# Micro_Controller.net
KiCad netlist of a schematic drawn in Altium Designer
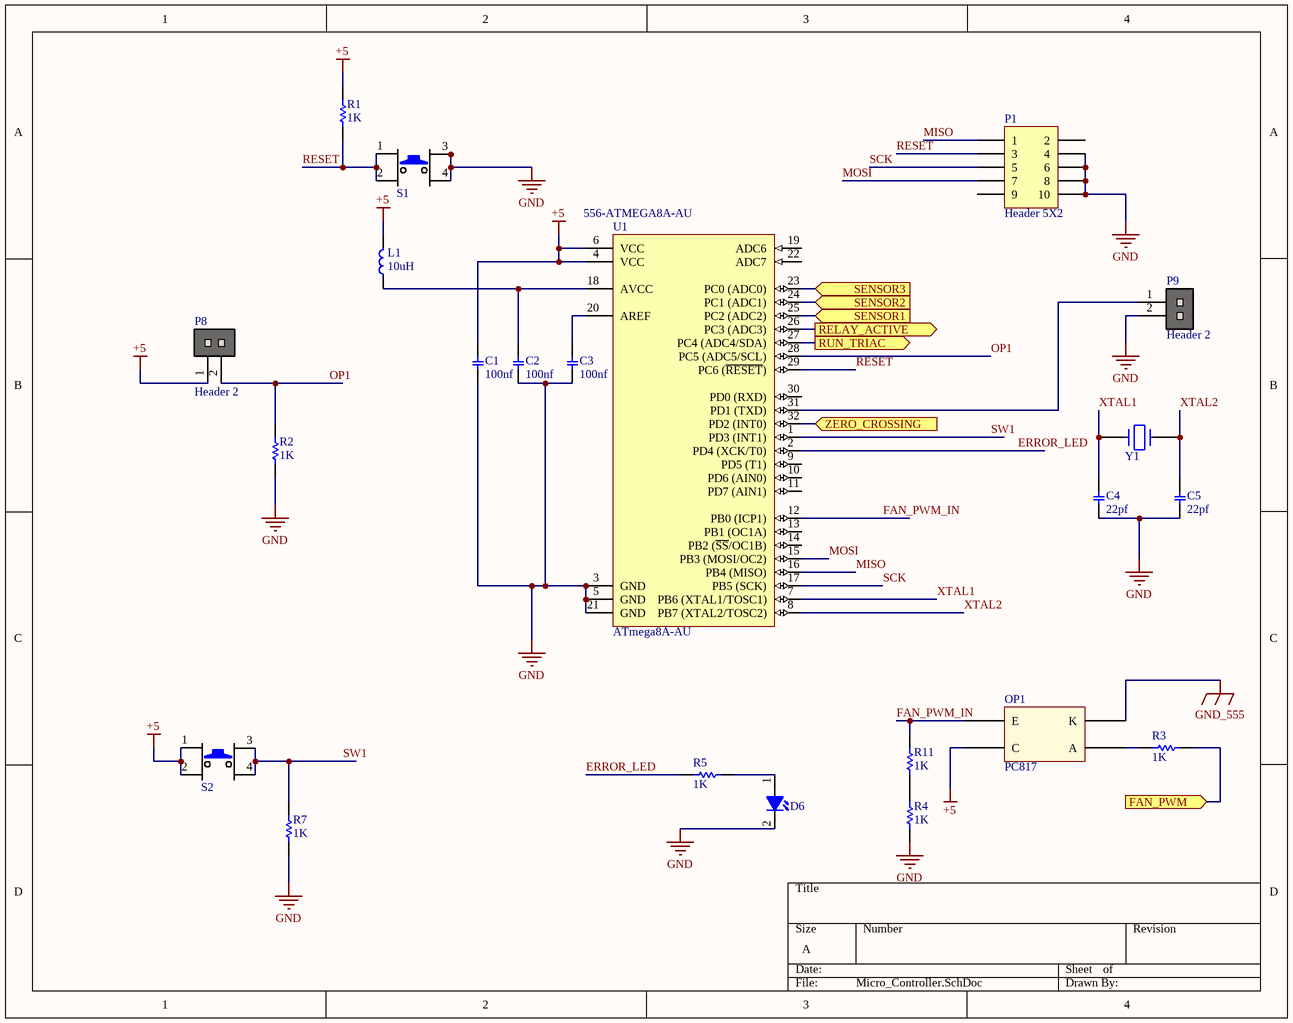
[diagram p0: Micro_Controller.SchDoc]

(export (version "E")
  (design (tool "Eeschema 10.0.6"))
  (components
    (comp (ref "C1")
      (value "100nf")
      (footprint "C1206")
      (description "Capacitor C SMD 1206")
      (libsource (lib "Capacitor") (part "Capacitor C SMD 1206"))
    )
    (comp (ref "C2")
      (value "100nf")
      (footprint "C1206")
      (description "Capacitor C SMD 1206")
      (libsource (lib "Capacitor") (part "Capacitor C SMD 1206"))
    )
    (comp (ref "C3")
      (value "100nf")
      (footprint "C1206")
      (description "Capacitor C SMD 1206")
      (libsource (lib "Capacitor") (part "Capacitor C SMD 1206"))
    )
    (comp (ref "C4")
      (value "22pf")
      (footprint "C1206")
      (description "Capacitor C SMD 1206")
      (libsource (lib "Capacitor") (part "Capacitor C SMD 1206"))
    )
    (comp (ref "C5")
      (value "22pf")
      (footprint "C1206")
      (description "Capacitor C SMD 1206")
      (libsource (lib "Capacitor") (part "Capacitor C SMD 1206"))
    )
    (comp (ref "D6")
      (value "LED THD 3mm")
      (footprint "LED THD 3mm (Green)")
      (libsource (lib "LED") (part "LED THD 3mm"))
    )
    (comp (ref "L1")
      (value "10uH")
      (footprint "L1206")
      (description "Inductor SMD NC 1206")
      (libsource (lib "Inductor") (part "Inductor SMD NC 1206"))
    )
    (comp (ref "OP1")
      (value "PC817")
      (footprint "PC817 SMD")
      (description "PC817 optocpler")
      (libsource (lib "IC") (part "PC817"))
    )
    (comp (ref "P1")
      (value "Header 5X2")
      (footprint "HDR2X5")
      (description "Header, 5-Pin, Dual row")
      (fields (field (name "PUBLISHER") "Altium Limited"))
      (libsource (lib "Miscellaneous Connectors") (part "Header 5X2"))
    )
    (comp (ref "P8")
      (value "Header 2")
      (footprint "HDR 1X2")
      (description "Header, 2-Pin")
      (libsource (lib "Header") (part "Header 2"))
    )
    (comp (ref "P9")
      (value "Header 2")
      (footprint "HDR 1X2")
      (description "Header, 2-Pin")
      (libsource (lib "") (part "Header 2_1"))
    )
    (comp (ref "R1")
      (value "1K")
      (footprint "SMD-1206-RES")
      (description "Resistor SMD 1206")
      (libsource (lib "Resistor") (part "Resistor SMD 1206"))
    )
    (comp (ref "R2")
      (value "1K")
      (footprint "SMD-1206-RES")
      (description "Resistor SMD 1206")
      (libsource (lib "Resistor") (part "Resistor SMD 1206"))
    )
    (comp (ref "R3")
      (value "1K")
      (footprint "SMD-1206-RES")
      (description "Resistor SMD 1206")
      (libsource (lib "Resistor") (part "Resistor SMD 1206"))
    )
    (comp (ref "R4")
      (value "1K")
      (footprint "SMD-1206-RES")
      (description "Resistor SMD 1206")
      (libsource (lib "Resistor") (part "Resistor SMD 1206"))
    )
    (comp (ref "R5")
      (value "1K")
      (footprint "SMD-1206-RES")
      (description "Resistor SMD 1206")
      (libsource (lib "Resistor") (part "Resistor SMD 1206"))
    )
    (comp (ref "R7")
      (value "1K")
      (footprint "SMD-1206-RES")
      (description "Resistor SMD 1206")
      (libsource (lib "Resistor") (part "Resistor SMD 1206"))
    )
    (comp (ref "R11")
      (value "1K")
      (footprint "SMD-1206-RES")
      (description "Resistor SMD 1206")
      (libsource (lib "Resistor") (part "Resistor SMD 1206"))
    )
    (comp (ref "S1")
      (value "SW_PB4 THD")
      (footprint "SW THD 4 PIN (6)")
      (libsource (lib "Micro Switch") (part "SW_PB4 THD"))
    )
    (comp (ref "S2")
      (value "SW_PB4 THD")
      (footprint "SW THD 4 PIN (6)")
      (libsource (lib "Micro Switch") (part "SW_PB4 THD"))
    )
    (comp (ref "U1")
      (value "ATmega8A-AU")
      (footprint "32A_N")
      (fields (field (name "SUPPLIER PART NUMBER 1") "556-ATMEGA8A-AU"))
      (libsource (lib "Atmel Microcontroller 8-Bit megaAVR") (part "ATmega8A-AU"))
    )
    (comp (ref "Y1")
      (value "Crystal")
      (footprint "Crystal 5 16MHZ")
      (libsource (lib "Practical") (part "Crystal"))
    )
  )
  (nets
    (net (code "1") (name "+5") (class "Default")
      (node (ref "C1") (pin "2") (pinfunction "2_2") (pintype "passive"))
      (node (ref "L1") (pin "2") (pinfunction "2_2") (pintype "passive"))
      (node (ref "OP1") (pin "4") (pinfunction "C_4") (pintype "passive"))
      (node (ref "P8") (pin "1") (pinfunction "1_1") (pintype "passive"))
      (node (ref "R1") (pin "2") (pinfunction "2_2") (pintype "passive"))
      (node (ref "S2") (pin "1") (pinfunction "1_1") (pintype "passive"))
      (node (ref "S2") (pin "2") (pinfunction "2_2") (pintype "passive"))
      (node (ref "U1") (pin "4") (pinfunction "VCC_4") (pintype "power_in"))
      (node (ref "U1") (pin "6") (pinfunction "VCC_6") (pintype "power_in"))
    )
    (net (code "2") (name "/ERROR_LED") (class "Default")
      (node (ref "R5") (pin "1") (pinfunction "1_1") (pintype "passive"))
      (node (ref "U1") (pin "2") (pinfunction "PD4_(XCK/T0)_2") (pintype "bidirectional"))
    )
    (net (code "3") (name "/FAN_PWM") (class "Default")
      (node (ref "R3") (pin "2") (pinfunction "2_2") (pintype "passive"))
    )
    (net (code "4") (name "/FAN_PWM_IN") (class "Default")
      (node (ref "OP1") (pin "3") (pinfunction "E_3") (pintype "passive"))
      (node (ref "R11") (pin "2") (pinfunction "2_2") (pintype "passive"))
      (node (ref "U1") (pin "12") (pinfunction "PB0_(ICP1)_12") (pintype "bidirectional"))
    )
    (net (code "5") (name "/MISO") (class "Default")
      (node (ref "P1") (pin "1") (pinfunction "1_1") (pintype "passive"))
      (node (ref "U1") (pin "16") (pinfunction "PB4_(MISO)_16") (pintype "bidirectional"))
    )
    (net (code "6") (name "/MOSI") (class "Default")
      (node (ref "P1") (pin "7") (pinfunction "7_7") (pintype "passive"))
      (node (ref "U1") (pin "15") (pinfunction "PB3_(MOSI/OC2)_15") (pintype "bidirectional"))
    )
    (net (code "7") (name "/OP1") (class "Default")
      (node (ref "P8") (pin "2") (pinfunction "2_2") (pintype "passive"))
      (node (ref "R2") (pin "2") (pinfunction "2_2") (pintype "passive"))
      (node (ref "U1") (pin "28") (pinfunction "PC5_(ADC5/SCL)_28") (pintype "bidirectional"))
    )
    (net (code "8") (name "/RELAY_ACTIVE") (class "Default")
      (node (ref "U1") (pin "26") (pinfunction "PC3_(ADC3)_26") (pintype "bidirectional"))
    )
    (net (code "9") (name "/RESET") (class "Default")
      (node (ref "P1") (pin "3") (pinfunction "3_3") (pintype "passive"))
      (node (ref "R1") (pin "1") (pinfunction "1_1") (pintype "passive"))
      (node (ref "S1") (pin "1") (pinfunction "1_1") (pintype "passive"))
      (node (ref "S1") (pin "2") (pinfunction "2_2") (pintype "passive"))
      (node (ref "U1") (pin "29") (pinfunction "PC6_(~{RESET})_29") (pintype "bidirectional"))
    )
    (net (code "10") (name "/RUN_TRIAC") (class "Default")
      (node (ref "U1") (pin "27") (pinfunction "PC4_(ADC4/SDA)_27") (pintype "bidirectional"))
    )
    (net (code "11") (name "/SCK") (class "Default")
      (node (ref "P1") (pin "5") (pinfunction "5_5") (pintype "passive"))
      (node (ref "U1") (pin "17") (pinfunction "PB5_(SCK)_17") (pintype "bidirectional"))
    )
    (net (code "12") (name "/SENSOR1") (class "Default")
      (node (ref "U1") (pin "25") (pinfunction "PC2_(ADC2)_25") (pintype "bidirectional"))
    )
    (net (code "13") (name "/SENSOR2") (class "Default")
      (node (ref "U1") (pin "24") (pinfunction "PC1_(ADC1)_24") (pintype "bidirectional"))
    )
    (net (code "14") (name "/SENSOR3") (class "Default")
      (node (ref "U1") (pin "23") (pinfunction "PC0_(ADC0)_23") (pintype "bidirectional"))
    )
    (net (code "15") (name "/SW1") (class "Default")
      (node (ref "R7") (pin "2") (pinfunction "2_2") (pintype "passive"))
      (node (ref "S2") (pin "3") (pinfunction "3_3") (pintype "passive"))
      (node (ref "S2") (pin "4") (pinfunction "4_4") (pintype "passive"))
      (node (ref "U1") (pin "1") (pinfunction "PD3_(INT1)_1") (pintype "bidirectional"))
    )
    (net (code "16") (name "/XTAL1") (class "Default")
      (node (ref "C4") (pin "2") (pinfunction "2_2") (pintype "passive"))
      (node (ref "U1") (pin "7") (pinfunction "PB6_(XTAL1/TOSC1)_7") (pintype "bidirectional"))
      (node (ref "Y1") (pin "1") (pinfunction "1_1") (pintype "passive"))
    )
    (net (code "17") (name "/XTAL2") (class "Default")
      (node (ref "C5") (pin "2") (pinfunction "2_2") (pintype "passive"))
      (node (ref "U1") (pin "8") (pinfunction "PB7_(XTAL2/TOSC2)_8") (pintype "bidirectional"))
      (node (ref "Y1") (pin "2") (pinfunction "2_2") (pintype "passive"))
    )
    (net (code "18") (name "/ZERO_CROSSING") (class "Default")
      (node (ref "U1") (pin "32") (pinfunction "PD2_(INT0)_32") (pintype "bidirectional"))
    )
    (net (code "19") (name "GND") (class "Default")
      (node (ref "C1") (pin "1") (pinfunction "1_1") (pintype "passive"))
      (node (ref "C2") (pin "1") (pinfunction "1_1") (pintype "passive"))
      (node (ref "C3") (pin "1") (pinfunction "1_1") (pintype "passive"))
      (node (ref "C4") (pin "1") (pinfunction "1_1") (pintype "passive"))
      (node (ref "C5") (pin "1") (pinfunction "1_1") (pintype "passive"))
      (node (ref "D6") (pin "2") (pinfunction "CATHODE_2") (pintype "passive"))
      (node (ref "P1") (pin "10") (pinfunction "10_10") (pintype "passive"))
      (node (ref "P1") (pin "4") (pinfunction "4_4") (pintype "passive"))
      (node (ref "P1") (pin "6") (pinfunction "6_6") (pintype "passive"))
      (node (ref "P1") (pin "8") (pinfunction "8_8") (pintype "passive"))
      (node (ref "P9") (pin "2") (pinfunction "2_2") (pintype "passive"))
      (node (ref "R2") (pin "1") (pinfunction "1_1") (pintype "passive"))
      (node (ref "R4") (pin "1") (pinfunction "1_1") (pintype "passive"))
      (node (ref "R7") (pin "1") (pinfunction "1_1") (pintype "passive"))
      (node (ref "S1") (pin "3") (pinfunction "3_3") (pintype "passive"))
      (node (ref "S1") (pin "4") (pinfunction "4_4") (pintype "passive"))
      (node (ref "U1") (pin "21") (pinfunction "GND_21") (pintype "power_in"))
      (node (ref "U1") (pin "3") (pinfunction "GND_3") (pintype "power_in"))
      (node (ref "U1") (pin "5") (pinfunction "GND_5") (pintype "power_in"))
    )
    (net (code "20") (name "GND_555") (class "Default")
      (node (ref "OP1") (pin "2") (pinfunction "K_2") (pintype "passive"))
    )
    (net (code "21") (name "Net-(D6-ANODE)") (class "Default")
      (node (ref "D6") (pin "1") (pinfunction "ANODE_1") (pintype "passive"))
      (node (ref "R5") (pin "2") (pinfunction "2_2") (pintype "passive"))
    )
    (net (code "22") (name "Net-(OP1-A)") (class "Default")
      (node (ref "OP1") (pin "1") (pinfunction "A_1") (pintype "passive"))
      (node (ref "R3") (pin "1") (pinfunction "1_1") (pintype "passive"))
    )
    (net (code "23") (name "Net-(R11-Pad1)") (class "Default")
      (node (ref "R11") (pin "1") (pinfunction "1_1") (pintype "passive"))
      (node (ref "R4") (pin "2") (pinfunction "2_2") (pintype "passive"))
    )
    (net (code "24") (name "Net-(U1-AREF)") (class "Default")
      (node (ref "C3") (pin "2") (pinfunction "2_2") (pintype "passive"))
      (node (ref "U1") (pin "20") (pinfunction "AREF_20") (pintype "power_in"))
    )
    (net (code "25") (name "Net-(U1-AVCC)") (class "Default")
      (node (ref "C2") (pin "2") (pinfunction "2_2") (pintype "passive"))
      (node (ref "L1") (pin "1") (pinfunction "1_1") (pintype "passive"))
      (node (ref "U1") (pin "18") (pinfunction "AVCC_18") (pintype "power_in"))
    )
    (net (code "26") (name "Net-(U1-PD1_(TXD))") (class "Default")
      (node (ref "P9") (pin "1") (pinfunction "1_1") (pintype "passive"))
      (node (ref "U1") (pin "31") (pinfunction "PD1_(TXD)_31") (pintype "bidirectional"))
    )
    (net (code "27") (name "unconnected-(P1-Pad2)") (class "Default")
      (node (ref "P1") (pin "2") (pinfunction "2_2") (pintype "passive"))
    )
    (net (code "28") (name "unconnected-(P1-Pad9)") (class "Default")
      (node (ref "P1") (pin "9") (pinfunction "9_9") (pintype "passive"))
    )
    (net (code "29") (name "unconnected-(U1-ADC6-Pad19)") (class "Default")
      (node (ref "U1") (pin "19") (pinfunction "ADC6_19") (pintype "input"))
    )
    (net (code "30") (name "unconnected-(U1-ADC7-Pad22)") (class "Default")
      (node (ref "U1") (pin "22") (pinfunction "ADC7_22") (pintype "input"))
    )
    (net (code "31") (name "unconnected-(U1-PB1_(OC1A)-Pad13)") (class "Default")
      (node (ref "U1") (pin "13") (pinfunction "PB1_(OC1A)_13") (pintype "bidirectional"))
    )
    (net (code "32") (name "unconnected-(U1-PB2_(~{SS}{slash}OC1B)-Pad14)") (class "Default")
      (node (ref "U1") (pin "14") (pinfunction "PB2_(~{SS}/OC1B)_14") (pintype "bidirectional"))
    )
    (net (code "33") (name "unconnected-(U1-PD0_(RXD)-Pad30)") (class "Default")
      (node (ref "U1") (pin "30") (pinfunction "PD0_(RXD)_30") (pintype "bidirectional"))
    )
    (net (code "34") (name "unconnected-(U1-PD5_(T1)-Pad9)") (class "Default")
      (node (ref "U1") (pin "9") (pinfunction "PD5_(T1)_9") (pintype "bidirectional"))
    )
    (net (code "35") (name "unconnected-(U1-PD6_(AIN0)-Pad10)") (class "Default")
      (node (ref "U1") (pin "10") (pinfunction "PD6_(AIN0)_10") (pintype "bidirectional"))
    )
    (net (code "36") (name "unconnected-(U1-PD7_(AIN1)-Pad11)") (class "Default")
      (node (ref "U1") (pin "11") (pinfunction "PD7_(AIN1)_11") (pintype "bidirectional"))
    )
  )
)
